# machnguon.net
KiCad netlist of a schematic drawn in Altium Designer
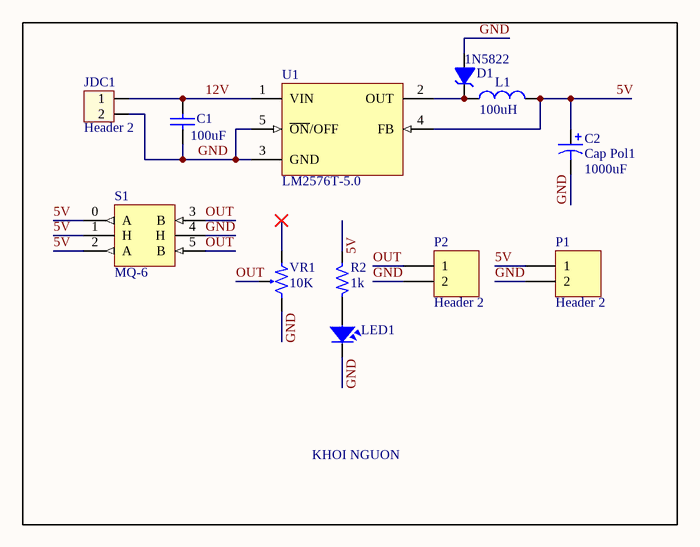
[diagram p0: machnguon.SchDoc]

(export (version "E")
  (design (tool "Eeschema 10.0.6"))
  (components
    (comp (ref "C1")
      (value "100uF")
      (footprint "CP1.5/2.5")
      (description "Capacitor")
      (fields (field (name "Comment") "Cap") (field (name "PUBLISHER") "Altium Limited"))
      (libsource (lib "Miscellaneous Devices") (part "Cap"))
    )
    (comp (ref "C2")
      (value "Cap Pol1")
      (footprint "CP2/4")
      (description "Polarized Capacitor (Radial)")
      (fields (field (name "ALTIUM_VALUE") "1000uF") (field (name "PUBLISHER") "Altium Limited"))
      (libsource (lib "Miscellaneous Devices") (part "Cap Pol1"))
    )
    (comp (ref "D1")
      (value "1N5822")
      (footprint "DZ0.5A")
      (description "Diode Zenner")
      (libsource (lib "syhaunguyen") (part "DZ"))
    )
    (comp (ref "JDC1")
      (value "Header 2")
      (footprint "HED2")
      (description "Header 2 (Green)")
      (libsource (lib "syhaunguyen") (part "Hed2"))
    )
    (comp (ref "L1")
      (value "100uH")
      (footprint "L01")
      (description "Inductor")
      (libsource (lib "syhaunguyen") (part "L1"))
    )
    (comp (ref "LED1")
      (value "~")
      (footprint "LED-3")
      (description "Led  Vuong")
      (libsource (lib "syhaunguyen") (part "LED"))
    )
    (comp (ref "P1")
      (value "Header 2")
      (footprint "HDR1X2")
      (description "Header, 2-Pin")
      (fields (field (name "PUBLISHER") "Altium Limited"))
      (libsource (lib "Miscellaneous Connectors") (part "Header 2"))
    )
    (comp (ref "P2")
      (value "Header 2")
      (footprint "HDR1X2")
      (description "Header, 2-Pin")
      (fields (field (name "PUBLISHER") "Altium Limited"))
      (libsource (lib "Miscellaneous Connectors") (part "Header 2"))
    )
    (comp (ref "R2")
      (value "1k")
      (footprint "SM-0805")
      (description "Resistor 1/4W")
      (libsource (lib "syhaunguyen") (part "R"))
    )
    (comp (ref "S1")
      (value "MQ-6")
      (footprint "MQ6")
      (description "Gas and Smoke Sensor")
      (libsource (lib "MyLibAltium") (part "MQ-6"))
    )
    (comp (ref "U1")
      (value "LM2576T-5.0")
      (footprint "TO170P1420-6N")
      (description "SIMPLE SWITCHER; 3A Step-Down Voltage Regulator")
      (fields
        (field (name "MANUFACTURER") "National Semiconductor")
        (field (name "DIGIKEYPARTNUMBER") "LM2576T-5.0-ND")
        (field (name "PUBLISHER") "Altium Limited")
      )
      (libsource (lib "General IC") (part "LM2576T-5.0"))
    )
    (comp (ref "VR1")
      (value "10K")
      (footprint "VR1")
      (description "Var Resistor")
      (libsource (lib "syhaunguyen") (part "VR1"))
    )
  )
  (nets
    (net (code "1") (name "/5V") (class "Default")
      (node (ref "C2") (pin "1") (pinfunction "1_1") (pintype "passive"))
      (node (ref "L1") (pin "2") (pinfunction "2_2") (pintype "passive"))
      (node (ref "P1") (pin "1") (pinfunction "1_1") (pintype "passive"))
      (node (ref "R2") (pin "1") (pinfunction "1_1") (pintype "passive"))
      (node (ref "S1") (pin "0") (pinfunction "A_0") (pintype "output"))
      (node (ref "S1") (pin "1") (pinfunction "H_1") (pintype "power_in"))
      (node (ref "S1") (pin "2") (pinfunction "A_2") (pintype "output"))
      (node (ref "U1") (pin "4") (pinfunction "FB_4") (pintype "input"))
    )
    (net (code "2") (name "/12V") (class "Default")
      (node (ref "C1") (pin "2") (pinfunction "2_2") (pintype "passive"))
      (node (ref "JDC1") (pin "1") (pinfunction "1_1") (pintype "passive"))
      (node (ref "U1") (pin "1") (pinfunction "VIN_1") (pintype "power_in"))
    )
    (net (code "3") (name "/GND") (class "Default")
      (node (ref "C1") (pin "1") (pinfunction "1_1") (pintype "passive"))
      (node (ref "C2") (pin "2") (pinfunction "2_2") (pintype "passive"))
      (node (ref "D1") (pin "1") (pinfunction "A_1") (pintype "passive"))
      (node (ref "JDC1") (pin "2") (pinfunction "2_2") (pintype "passive"))
      (node (ref "LED1") (pin "2") (pinfunction "2_2") (pintype "passive"))
      (node (ref "P1") (pin "2") (pinfunction "2_2") (pintype "passive"))
      (node (ref "P2") (pin "2") (pinfunction "2_2") (pintype "passive"))
      (node (ref "S1") (pin "4") (pinfunction "H_4") (pintype "power_in"))
      (node (ref "U1") (pin "3") (pinfunction "GND_3") (pintype "power_in"))
      (node (ref "U1") (pin "5") (pinfunction "~{ON}/OFF_5") (pintype "input"))
      (node (ref "VR1") (pin "3") (pinfunction "3_3") (pintype "passive"))
    )
    (net (code "4") (name "/OUT") (class "Default")
      (node (ref "P2") (pin "1") (pinfunction "1_1") (pintype "passive"))
      (node (ref "S1") (pin "3") (pinfunction "B_3") (pintype "input"))
      (node (ref "S1") (pin "5") (pinfunction "B_5") (pintype "input"))
      (node (ref "VR1") (pin "2") (pinfunction "2_2") (pintype "passive"))
    )
    (net (code "5") (name "Net-(D1-K)") (class "Default")
      (node (ref "D1") (pin "2") (pinfunction "K_2") (pintype "passive"))
      (node (ref "L1") (pin "1") (pinfunction "1_1") (pintype "passive"))
      (node (ref "U1") (pin "2") (pinfunction "OUT_2") (pintype "power_in"))
    )
    (net (code "6") (name "Net-(LED1-Pad1)") (class "Default")
      (node (ref "LED1") (pin "1") (pinfunction "1_1") (pintype "passive"))
      (node (ref "R2") (pin "2") (pinfunction "2_2") (pintype "passive"))
    )
    (net (code "7") (name "unconnected-(VR1-Pad1)") (class "Default")
      (node (ref "VR1") (pin "1") (pinfunction "1_1") (pintype "passive+no_connect"))
    )
  )
)
